# Output_Driver.net
KiCad netlist of a schematic drawn in Altium Designer
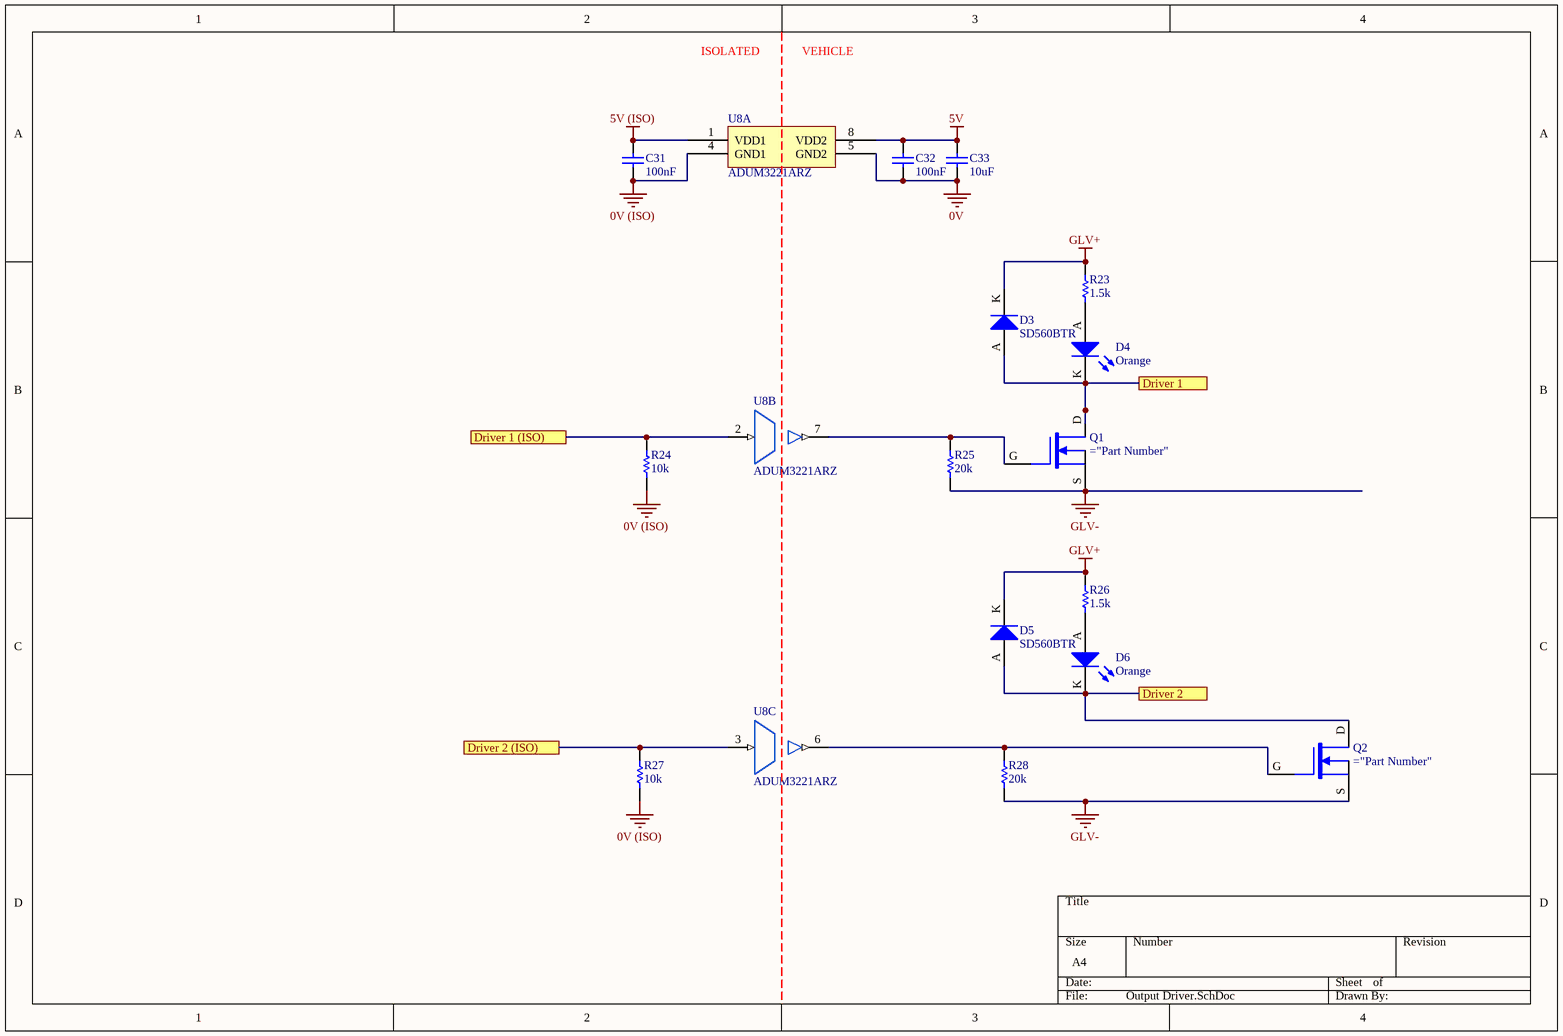
[diagram p0: Output Driver.SchDoc]

(export (version "E")
  (design (tool "Eeschema 10.0.6"))
  (components
    (comp (ref "C31")
      (value "100nF")
      (footprint "0805")
      (fields
        (field (name "PART NUMBER") "GCM21BR71E104KA37L")
        (field (name "TOLERANCE") "10%")
        (field (name "MANUFACTURER") "muRata")
      )
      (libsource (lib "ts_20-standard-library") (part "Capacitor"))
    )
    (comp (ref "C32")
      (value "100nF")
      (footprint "0805")
      (fields
        (field (name "PART NUMBER") "GCM21BR71E104KA37L")
        (field (name "TOLERANCE") "10%")
        (field (name "MANUFACTURER") "muRata")
      )
      (libsource (lib "ts_20-standard-library") (part "Capacitor"))
    )
    (comp (ref "C33")
      (value "10uF")
      (footprint "0805")
      (fields
        (field (name "PART NUMBER") "GRM21BR6YA106KE43L")
        (field (name "TOLERANCE") "10%")
        (field (name "MANUFACTURER") "muRata")
      )
      (libsource (lib "ts_20-standard-library") (part "Capacitor"))
    )
    (comp (ref "D3")
      (value "SD560BTR")
      (footprint "SMB Diode")
      (description "1.2V_F 600V 5A SMB")
      (fields
        (field (name "MANUFACTURER") "SMC Diode Solutions")
        (field (name "DIGIKEY PART NUMBER") "1655-1530-2-ND")
      )
      (libsource (lib "ts_20-standard-library") (part "Diode"))
    )
    (comp (ref "D4")
      (value "Orange")
      (footprint "0805 LED")
      (description "Orange LED Indication - Discrete 1.75V 0805 (2012 Metric)")
      (fields (field (name "PART NUMBER") "SML-211DTT86") (field (name "MANUFACTURER") "ROHM Semiconductor"))
      (libsource (lib "ts_20-standard-library") (part "LED"))
    )
    (comp (ref "D5")
      (value "SD560BTR")
      (footprint "SMB Diode")
      (description "1.2V_F 600V 5A SMB")
      (fields
        (field (name "MANUFACTURER") "SMC Diode Solutions")
        (field (name "DIGIKEY PART NUMBER") "1655-1530-2-ND")
      )
      (libsource (lib "ts_20-standard-library") (part "Diode"))
    )
    (comp (ref "D6")
      (value "Orange")
      (footprint "0805 LED")
      (description "Orange LED Indication - Discrete 1.75V 0805 (2012 Metric)")
      (fields (field (name "PART NUMBER") "SML-211DTT86") (field (name "MANUFACTURER") "ROHM Semiconductor"))
      (libsource (lib "ts_20-standard-library") (part "LED"))
    )
    (comp (ref "Q1")
      (value "~")
      (footprint "SOT-343_N")
      (fields (field (name "PUBLISHER") "Altium Limited"))
      (libsource (lib "analogue") (part "MOSFET-N"))
    )
    (comp (ref "Q2")
      (value "~")
      (footprint "SOT-343_N")
      (fields (field (name "PUBLISHER") "Altium Limited"))
      (libsource (lib "analogue") (part "MOSFET-N"))
    )
    (comp (ref "R23")
      (value "1.5k")
      (footprint "0805")
      (fields
        (field (name "PART NUMBER") "RC0805FR071K5L")
        (field (name "MANUFACTURER") "YAGEO")
        (field (name "TOLERANCE") "0.01")
      )
      (libsource (lib "ts_20-standard-library") (part "Resistor"))
    )
    (comp (ref "R24")
      (value "10k")
      (footprint "0805")
      (fields
        (field (name "PART NUMBER") "RC0805FR0710KL")
        (field (name "MANUFACTURER") "YAGEO")
        (field (name "TOLERANCE") "0.01")
      )
      (libsource (lib "ts_20-standard-library") (part "Resistor"))
    )
    (comp (ref "R25")
      (value "20k")
      (footprint "0805")
      (fields
        (field (name "PART NUMBER") "RC0805FR0720KL")
        (field (name "MANUFACTURER") "YAGEO")
        (field (name "TOLERANCE") "0.01")
      )
      (libsource (lib "ts_20-standard-library") (part "Resistor"))
    )
    (comp (ref "R26")
      (value "1.5k")
      (footprint "0805")
      (fields
        (field (name "PART NUMBER") "RC0805FR071K5L")
        (field (name "MANUFACTURER") "YAGEO")
        (field (name "TOLERANCE") "0.01")
      )
      (libsource (lib "ts_20-standard-library") (part "Resistor"))
    )
    (comp (ref "R27")
      (value "10k")
      (footprint "0805")
      (fields
        (field (name "PART NUMBER") "RC0805FR0710KL")
        (field (name "MANUFACTURER") "YAGEO")
        (field (name "TOLERANCE") "0.01")
      )
      (libsource (lib "ts_20-standard-library") (part "Resistor"))
    )
    (comp (ref "R28")
      (value "20k")
      (footprint "0805")
      (fields
        (field (name "PART NUMBER") "RC0805FR0720KL")
        (field (name "MANUFACTURER") "YAGEO")
        (field (name "TOLERANCE") "0.01")
      )
      (libsource (lib "ts_20-standard-library") (part "Resistor"))
    )
    (comp (ref "U8")
      (value "ADUM3221ARZ")
      (footprint "AD 8-SOIC")
      (description "4A Gate Driver Magnetic Coupling 2500Vrms 2 Channel 8-SOIC")
      (fields
        (field (name "MANUFACTURER") "Analog Devices")
        (field (name "DIGIKEY PART NUMBER") "ADUM3221ARZ-ND")
      )
      (libsource (lib "ts_20-standard-library") (part "ADuM3221"))
    )
  )
  (nets
    (net (code "1") (name "/Driver 1") (class "Default")
      (node (ref "D3") (pin "A") (pinfunction "A_A") (pintype "passive"))
      (node (ref "D4") (pin "K") (pinfunction "K_K") (pintype "passive"))
      (node (ref "Q1") (pin "D") (pinfunction "D_D") (pintype "passive"))
    )
    (net (code "2") (name "/Driver 1 (ISO)") (class "Default")
      (node (ref "R24") (pin "2") (pinfunction "2_2") (pintype "passive"))
      (node (ref "U8") (pin "2") (pinfunction "VIA_2") (pintype "input"))
    )
    (net (code "3") (name "/Driver 2") (class "Default")
      (node (ref "D5") (pin "A") (pinfunction "A_A") (pintype "passive"))
      (node (ref "D6") (pin "K") (pinfunction "K_K") (pintype "passive"))
      (node (ref "Q2") (pin "D") (pinfunction "D_D") (pintype "passive"))
    )
    (net (code "4") (name "/Driver 2 (ISO)") (class "Default")
      (node (ref "R27") (pin "2") (pinfunction "2_2") (pintype "passive"))
      (node (ref "U8") (pin "3") (pinfunction "VIA_3") (pintype "input"))
    )
    (net (code "5") (name "0V") (class "Default")
      (node (ref "C32") (pin "1") (pinfunction "1_1") (pintype "passive"))
      (node (ref "C33") (pin "1") (pinfunction "1_1") (pintype "passive"))
      (node (ref "U8") (pin "5") (pinfunction "GND2_5") (pintype "passive"))
    )
    (net (code "6") (name "0V (ISO)") (class "Default")
      (node (ref "C31") (pin "1") (pinfunction "1_1") (pintype "passive"))
      (node (ref "R24") (pin "1") (pinfunction "1_1") (pintype "passive"))
      (node (ref "R27") (pin "1") (pinfunction "1_1") (pintype "passive"))
      (node (ref "U8") (pin "4") (pinfunction "GND1_4") (pintype "passive"))
    )
    (net (code "7") (name "5V") (class "Default")
      (node (ref "C32") (pin "2") (pinfunction "2_2") (pintype "passive"))
      (node (ref "C33") (pin "2") (pinfunction "2_2") (pintype "passive"))
      (node (ref "U8") (pin "8") (pinfunction "VDD2_8") (pintype "passive"))
    )
    (net (code "8") (name "5V (ISO)") (class "Default")
      (node (ref "C31") (pin "2") (pinfunction "2_2") (pintype "passive"))
      (node (ref "U8") (pin "1") (pinfunction "VDD1_1") (pintype "passive"))
    )
    (net (code "9") (name "GLV+") (class "Default")
      (node (ref "D3") (pin "K") (pinfunction "K_K") (pintype "passive"))
      (node (ref "D5") (pin "K") (pinfunction "K_K") (pintype "passive"))
      (node (ref "R23") (pin "2") (pinfunction "2_2") (pintype "passive"))
      (node (ref "R26") (pin "2") (pinfunction "2_2") (pintype "passive"))
    )
    (net (code "10") (name "GLV-") (class "Default")
      (node (ref "Q1") (pin "S") (pinfunction "S_S") (pintype "passive"))
      (node (ref "Q2") (pin "S") (pinfunction "S_S") (pintype "passive"))
      (node (ref "R25") (pin "1") (pinfunction "1_1") (pintype "passive"))
      (node (ref "R28") (pin "1") (pinfunction "1_1") (pintype "passive"))
    )
    (net (code "11") (name "Net-(D4-PadA)") (class "Default")
      (node (ref "D4") (pin "A") (pinfunction "A_A") (pintype "passive"))
      (node (ref "R23") (pin "1") (pinfunction "1_1") (pintype "passive"))
    )
    (net (code "12") (name "Net-(D6-PadA)") (class "Default")
      (node (ref "D6") (pin "A") (pinfunction "A_A") (pintype "passive"))
      (node (ref "R26") (pin "1") (pinfunction "1_1") (pintype "passive"))
    )
    (net (code "13") (name "Net-(U8B-VOA)") (class "Default")
      (node (ref "Q1") (pin "G") (pinfunction "G_G") (pintype "passive"))
      (node (ref "R25") (pin "2") (pinfunction "2_2") (pintype "passive"))
      (node (ref "U8") (pin "7") (pinfunction "VOA_7") (pintype "output"))
    )
    (net (code "14") (name "Net-(U8C-VOA)") (class "Default")
      (node (ref "Q2") (pin "G") (pinfunction "G_G") (pintype "passive"))
      (node (ref "R28") (pin "2") (pinfunction "2_2") (pintype "passive"))
      (node (ref "U8") (pin "6") (pinfunction "VOA_6") (pintype "output"))
    )
  )
)
